# 1.net
KiCad netlist of a schematic drawn in Altium Designer
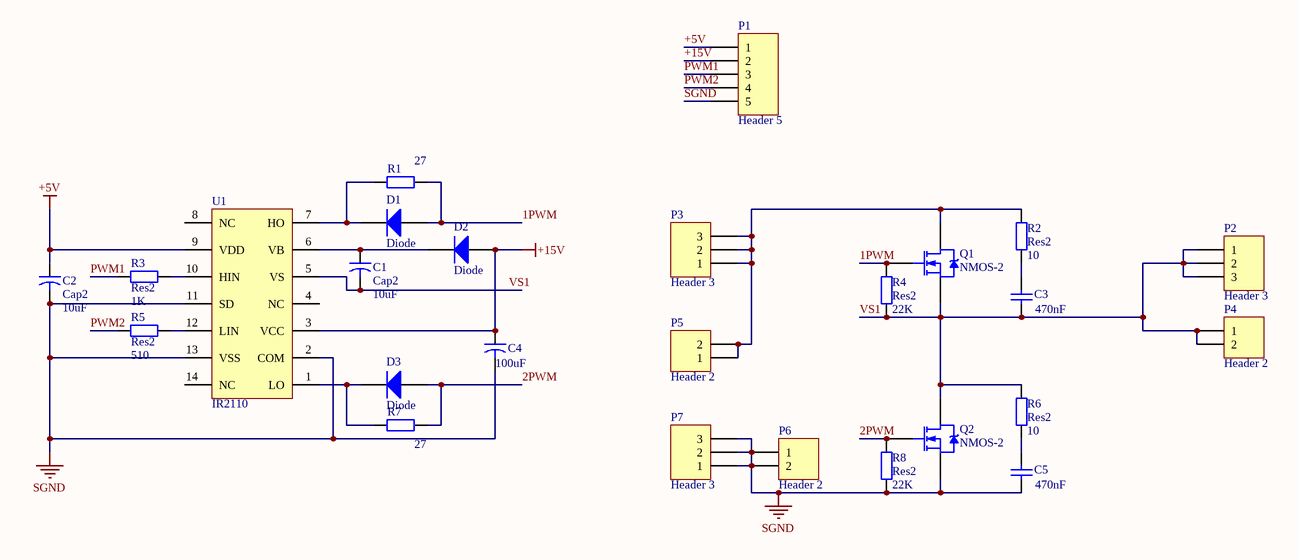
[diagram p0: 半桥模块1.SchDoc]

(export (version "E")
  (design (tool "Eeschema 10.0.6"))
  (components
    (comp (ref "C1")
      (value "Cap2")
      (footprint "C-10uF")
      (description "Capacitor")
      (fields (field (name "ALTIUM_VALUE") "10uF") (field (name "PUBLISHER") "Altium Limited"))
      (libsource (lib "Miscellaneous Devices") (part "Cap2"))
    )
    (comp (ref "C2")
      (value "Cap2")
      (footprint "C-10uF")
      (description "Capacitor")
      (fields (field (name "ALTIUM_VALUE") "10uF") (field (name "PUBLISHER") "Altium Limited"))
      (libsource (lib "Miscellaneous Devices") (part "Cap2"))
    )
    (comp (ref "C3")
      (value "470nF")
      (footprint "DuanZi")
      (description "Capacitor")
      (fields (field (name "Comment") "Cap") (field (name "PUBLISHER") "Altium Limited"))
      (libsource (lib "Miscellaneous Devices") (part "Cap"))
    )
    (comp (ref "C4")
      (value "100uF")
      (footprint "C-10uF")
      (description "Capacitor")
      (fields (field (name "Comment") "Cap2") (field (name "PUBLISHER") "Altium Limited"))
      (libsource (lib "Miscellaneous Devices") (part "Cap2"))
    )
    (comp (ref "C5")
      (value "470nF")
      (footprint "DuanZi")
      (description "Capacitor")
      (fields (field (name "Comment") "Cap") (field (name "PUBLISHER") "Altium Limited"))
      (libsource (lib "Miscellaneous Devices") (part "Cap"))
    )
    (comp (ref "D1")
      (value "Diode")
      (footprint "DO-41")
      (description "Default Diode")
      (fields (field (name "PUBLISHER") "Altium Limited"))
      (libsource (lib "Miscellaneous Devices") (part "Diode"))
    )
    (comp (ref "D2")
      (value "Diode")
      (footprint "DO-41")
      (description "Default Diode")
      (fields (field (name "PUBLISHER") "Altium Limited"))
      (libsource (lib "Miscellaneous Devices") (part "Diode"))
    )
    (comp (ref "D3")
      (value "Diode")
      (footprint "DO-41")
      (description "Default Diode")
      (fields (field (name "PUBLISHER") "Altium Limited"))
      (libsource (lib "Miscellaneous Devices") (part "Diode"))
    )
    (comp (ref "P1")
      (value "Header 5")
      (footprint "3.81mm_5")
      (description "Header, 5-Pin")
      (fields (field (name "PUBLISHER") "Altium Limited"))
      (libsource (lib "Miscellaneous Connectors") (part "Header 5"))
    )
    (comp (ref "P2")
      (value "Header 3")
      (footprint "HDR1X3")
      (description "Header, 3-Pin")
      (fields (field (name "PUBLISHER") "Altium Limited"))
      (libsource (lib "") (part "Header 3_1"))
    )
    (comp (ref "P3")
      (value "Header 3")
      (footprint "HDR1X3")
      (description "Header, 3-Pin")
      (fields (field (name "PUBLISHER") "Altium Limited"))
      (libsource (lib "Miscellaneous Connectors") (part "Header 3"))
    )
    (comp (ref "P4")
      (value "Header 2")
      (footprint "DuanZi")
      (description "Header, 2-Pin")
      (fields (field (name "PUBLISHER") "Altium Limited"))
      (libsource (lib "Miscellaneous Connectors") (part "Header 2"))
    )
    (comp (ref "P5")
      (value "Header 2")
      (footprint "DuanZi")
      (description "Header, 2-Pin")
      (fields (field (name "PUBLISHER") "Altium Limited"))
      (libsource (lib "") (part "Header 2_1"))
    )
    (comp (ref "P6")
      (value "Header 2")
      (footprint "DuanZi")
      (description "Header, 2-Pin")
      (fields (field (name "PUBLISHER") "Altium Limited"))
      (libsource (lib "Miscellaneous Connectors") (part "Header 2"))
    )
    (comp (ref "P7")
      (value "Header 3")
      (footprint "HDR1X3")
      (description "Header, 3-Pin")
      (fields (field (name "PUBLISHER") "Altium Limited"))
      (libsource (lib "Miscellaneous Connectors") (part "Header 3"))
    )
    (comp (ref "Q1")
      (value "NMOS-2")
      (footprint "MOS")
      (description "N-Channel Power MOSFET")
      (fields (field (name "PUBLISHER") "Altium Limited"))
      (libsource (lib "Miscellaneous Devices") (part "NMOS-2"))
    )
    (comp (ref "Q2")
      (value "NMOS-2")
      (footprint "MOS")
      (description "N-Channel Power MOSFET")
      (fields (field (name "PUBLISHER") "Altium Limited"))
      (libsource (lib "Miscellaneous Devices") (part "NMOS-2"))
    )
    (comp (ref "R1")
      (value "27")
      (footprint "AXIAL0.4-1/4W")
      (description "Resistor")
      (fields (field (name "Comment") "Res2") (field (name "PUBLISHER") "Altium Limited"))
      (libsource (lib "Miscellaneous Devices") (part "Res2"))
    )
    (comp (ref "R2")
      (value "Res2")
      (footprint "R_5W")
      (description "Resistor")
      (fields (field (name "ALTIUM_VALUE") "10") (field (name "PUBLISHER") "Altium Limited"))
      (libsource (lib "") (part "Res2_1"))
    )
    (comp (ref "R3")
      (value "Res2")
      (footprint "AXIAL0.4-1/4W")
      (description "Resistor")
      (fields (field (name "ALTIUM_VALUE") "1K") (field (name "PUBLISHER") "Altium Limited"))
      (libsource (lib "Miscellaneous Devices") (part "Res2"))
    )
    (comp (ref "R4")
      (value "Res2")
      (footprint "AXIAL0.4-1/4W")
      (description "Resistor")
      (fields (field (name "ALTIUM_VALUE") "22K") (field (name "PUBLISHER") "Altium Limited"))
      (libsource (lib "") (part "Res2_1"))
    )
    (comp (ref "R5")
      (value "Res2")
      (footprint "AXIAL0.4-1/4W")
      (description "Resistor")
      (fields (field (name "ALTIUM_VALUE") "510") (field (name "PUBLISHER") "Altium Limited"))
      (libsource (lib "Miscellaneous Devices") (part "Res2"))
    )
    (comp (ref "R6")
      (value "Res2")
      (footprint "R_5W")
      (description "Resistor")
      (fields (field (name "ALTIUM_VALUE") "10") (field (name "PUBLISHER") "Altium Limited"))
      (libsource (lib "") (part "Res2_1"))
    )
    (comp (ref "R7")
      (value "27")
      (footprint "AXIAL0.4-1/4W")
      (description "Resistor")
      (fields (field (name "Comment") "Res2") (field (name "PUBLISHER") "Altium Limited"))
      (libsource (lib "Miscellaneous Devices") (part "Res2"))
    )
    (comp (ref "R8")
      (value "Res2")
      (footprint "AXIAL0.4-1/4W")
      (description "Resistor")
      (fields (field (name "ALTIUM_VALUE") "22K") (field (name "PUBLISHER") "Altium Limited"))
      (libsource (lib "") (part "Res2_1"))
    )
    (comp (ref "U1")
      (value "IR2110")
      (footprint "DIP14-300_MH")
      (libsource (lib "My schlib") (part "IR2110"))
    )
  )
  (nets
    (net (code "1") (name "+5V") (class "Default")
      (node (ref "C2") (pin "1") (pinfunction "1_1") (pintype "passive"))
      (node (ref "P1") (pin "1") (pinfunction "1_1") (pintype "passive"))
      (node (ref "U1") (pin "9") (pinfunction "VDD_9") (pintype "passive"))
    )
    (net (code "2") (name "+15V") (class "Default")
      (node (ref "C4") (pin "1") (pinfunction "1_1") (pintype "passive"))
      (node (ref "D2") (pin "1") (pinfunction "A_1") (pintype "passive"))
      (node (ref "P1") (pin "2") (pinfunction "2_2") (pintype "passive"))
      (node (ref "U1") (pin "3") (pinfunction "VCC_3") (pintype "passive"))
    )
    (net (code "3") (name "/1PWM") (class "Default")
      (node (ref "D1") (pin "1") (pinfunction "A_1") (pintype "passive"))
      (node (ref "Q1") (pin "1") (pinfunction "G_1") (pintype "passive"))
      (node (ref "R1") (pin "2") (pinfunction "2_2") (pintype "passive"))
      (node (ref "R4") (pin "2") (pinfunction "2_2") (pintype "passive"))
    )
    (net (code "4") (name "/2PWM") (class "Default")
      (node (ref "D3") (pin "1") (pinfunction "A_1") (pintype "passive"))
      (node (ref "Q2") (pin "1") (pinfunction "G_1") (pintype "passive"))
      (node (ref "R7") (pin "2") (pinfunction "2_2") (pintype "passive"))
      (node (ref "R8") (pin "2") (pinfunction "2_2") (pintype "passive"))
    )
    (net (code "5") (name "/PWM1") (class "Default")
      (node (ref "P1") (pin "3") (pinfunction "3_3") (pintype "passive"))
      (node (ref "R3") (pin "1") (pinfunction "1_1") (pintype "passive"))
    )
    (net (code "6") (name "/PWM2") (class "Default")
      (node (ref "P1") (pin "4") (pinfunction "4_4") (pintype "passive"))
      (node (ref "R5") (pin "1") (pinfunction "1_1") (pintype "passive"))
    )
    (net (code "7") (name "/VS1") (class "Default")
      (node (ref "C1") (pin "2") (pinfunction "2_2") (pintype "passive"))
      (node (ref "C3") (pin "1") (pinfunction "1_1") (pintype "passive"))
      (node (ref "P2") (pin "1") (pinfunction "1_1") (pintype "passive"))
      (node (ref "P2") (pin "2") (pinfunction "2_2") (pintype "passive"))
      (node (ref "P2") (pin "3") (pinfunction "3_3") (pintype "passive"))
      (node (ref "P4") (pin "1") (pinfunction "1_1") (pintype "passive"))
      (node (ref "P4") (pin "2") (pinfunction "2_2") (pintype "passive"))
      (node (ref "Q1") (pin "3") (pinfunction "S_3") (pintype "passive"))
      (node (ref "Q2") (pin "2") (pinfunction "D_2") (pintype "passive"))
      (node (ref "R4") (pin "1") (pinfunction "1_1") (pintype "passive"))
      (node (ref "R6") (pin "2") (pinfunction "2_2") (pintype "passive"))
      (node (ref "U1") (pin "5") (pinfunction "VS_5") (pintype "passive"))
    )
    (net (code "8") (name "Net-(C3-Pad2)") (class "Default")
      (node (ref "C3") (pin "2") (pinfunction "2_2") (pintype "passive"))
      (node (ref "R2") (pin "1") (pinfunction "1_1") (pintype "passive"))
    )
    (net (code "9") (name "Net-(C5-Pad2)") (class "Default")
      (node (ref "C5") (pin "2") (pinfunction "2_2") (pintype "passive"))
      (node (ref "R6") (pin "1") (pinfunction "1_1") (pintype "passive"))
    )
    (net (code "10") (name "Net-(D1-K)") (class "Default")
      (node (ref "D1") (pin "2") (pinfunction "K_2") (pintype "passive"))
      (node (ref "R1") (pin "1") (pinfunction "1_1") (pintype "passive"))
      (node (ref "U1") (pin "7") (pinfunction "HO_7") (pintype "passive"))
    )
    (net (code "11") (name "Net-(D2-K)") (class "Default")
      (node (ref "C1") (pin "1") (pinfunction "1_1") (pintype "passive"))
      (node (ref "D2") (pin "2") (pinfunction "K_2") (pintype "passive"))
      (node (ref "U1") (pin "6") (pinfunction "VB_6") (pintype "passive"))
    )
    (net (code "12") (name "Net-(D3-K)") (class "Default")
      (node (ref "D3") (pin "2") (pinfunction "K_2") (pintype "passive"))
      (node (ref "R7") (pin "1") (pinfunction "1_1") (pintype "passive"))
      (node (ref "U1") (pin "1") (pinfunction "LO_1") (pintype "passive"))
    )
    (net (code "13") (name "Net-(Q1-D)") (class "Default")
      (node (ref "P3") (pin "1") (pinfunction "1_1") (pintype "passive"))
      (node (ref "P3") (pin "2") (pinfunction "2_2") (pintype "passive"))
      (node (ref "P3") (pin "3") (pinfunction "3_3") (pintype "passive"))
      (node (ref "P5") (pin "1") (pinfunction "1_1") (pintype "passive"))
      (node (ref "P5") (pin "2") (pinfunction "2_2") (pintype "passive"))
      (node (ref "Q1") (pin "2") (pinfunction "D_2") (pintype "passive"))
      (node (ref "R2") (pin "2") (pinfunction "2_2") (pintype "passive"))
    )
    (net (code "14") (name "Net-(U1-HIN)") (class "Default")
      (node (ref "R3") (pin "2") (pinfunction "2_2") (pintype "passive"))
      (node (ref "U1") (pin "10") (pinfunction "HIN_10") (pintype "passive"))
    )
    (net (code "15") (name "Net-(U1-LIN)") (class "Default")
      (node (ref "R5") (pin "2") (pinfunction "2_2") (pintype "passive"))
      (node (ref "U1") (pin "12") (pinfunction "LIN_12") (pintype "passive"))
    )
    (net (code "16") (name "SGND") (class "Default")
      (node (ref "C2") (pin "2") (pinfunction "2_2") (pintype "passive"))
      (node (ref "C4") (pin "2") (pinfunction "2_2") (pintype "passive"))
      (node (ref "C5") (pin "1") (pinfunction "1_1") (pintype "passive"))
      (node (ref "P1") (pin "5") (pinfunction "5_5") (pintype "passive"))
      (node (ref "P6") (pin "1") (pinfunction "1_1") (pintype "passive"))
      (node (ref "P6") (pin "2") (pinfunction "2_2") (pintype "passive"))
      (node (ref "P7") (pin "1") (pinfunction "1_1") (pintype "passive"))
      (node (ref "P7") (pin "2") (pinfunction "2_2") (pintype "passive"))
      (node (ref "P7") (pin "3") (pinfunction "3_3") (pintype "passive"))
      (node (ref "Q2") (pin "3") (pinfunction "S_3") (pintype "passive"))
      (node (ref "R8") (pin "1") (pinfunction "1_1") (pintype "passive"))
      (node (ref "U1") (pin "11") (pinfunction "SD_11") (pintype "passive"))
      (node (ref "U1") (pin "13") (pinfunction "VSS_13") (pintype "passive"))
      (node (ref "U1") (pin "2") (pinfunction "COM_2") (pintype "passive"))
    )
    (net (code "17") (name "unconnected-(U1-NC-Pad4)") (class "Default")
      (node (ref "U1") (pin "4") (pinfunction "NC_4") (pintype "passive"))
    )
    (net (code "18") (name "unconnected-(U1-NC-Pad8)") (class "Default")
      (node (ref "U1") (pin "8") (pinfunction "NC_8") (pintype "passive"))
    )
    (net (code "19") (name "unconnected-(U1-NC-Pad14)") (class "Default")
      (node (ref "U1") (pin "14") (pinfunction "NC_14") (pintype "passive"))
    )
  )
)
